# metronome_v1.net
KiCad netlist of a schematic drawn in EAGLE
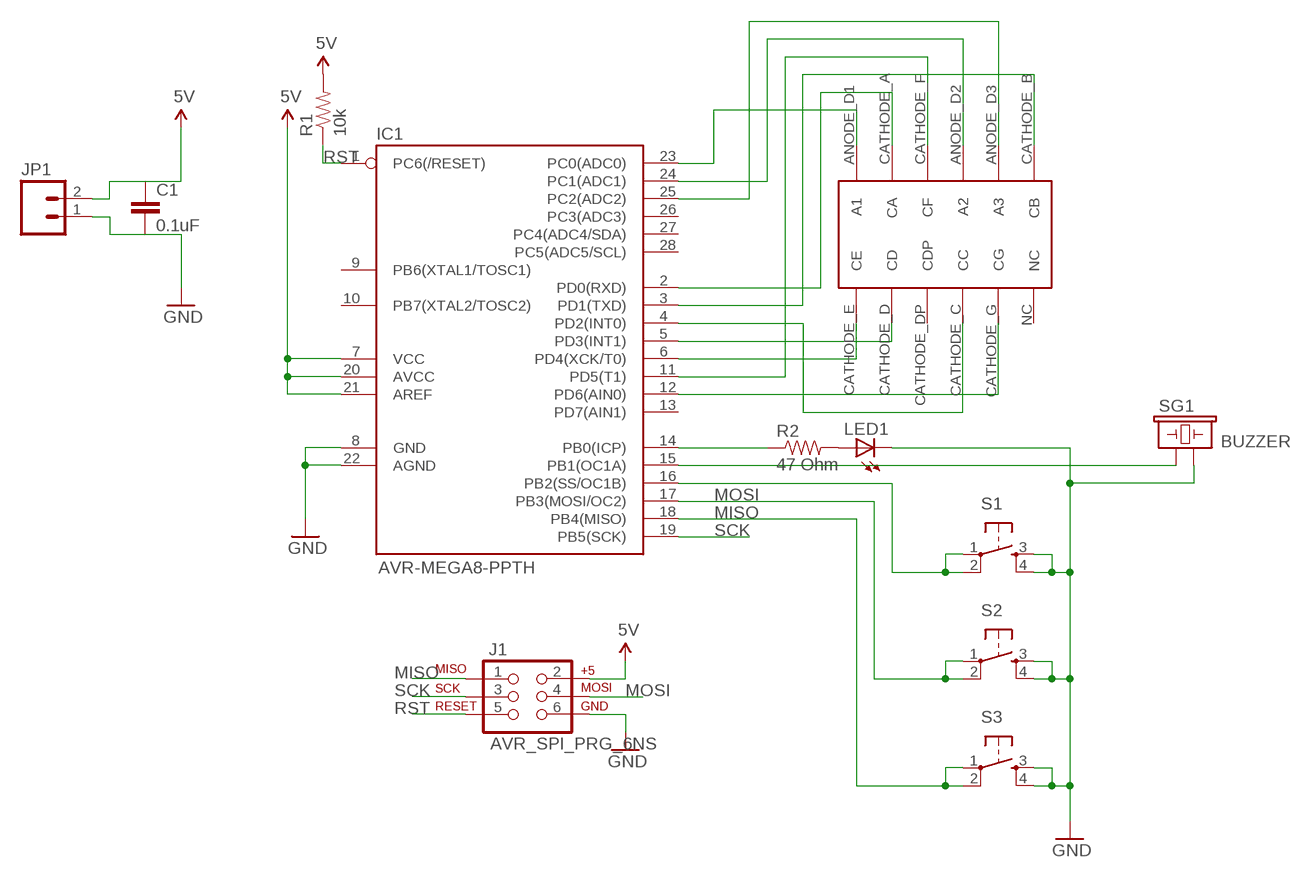
[diagram p0: schematic, sheet 1]

(export (version "E")
  (design (tool "Eeschema 10.0.6"))
  (components
    (comp (ref "C1")
      (value "0.1uF")
      (footprint "eagle-import:CAP-PTH-SMALL")
      (libsource (lib "eagle-import") (part "CAPPTH"))
    )
    (comp (ref "IC1")
      (value "AVR-MEGA8-PPTH")
      (footprint "eagle-import:DIL28-3")
      (libsource (lib "eagle-import") (part "AVR-MEGA8-PPTH"))
    )
    (comp (ref "J1")
      (value "AVR_SPI_PRG_6NS")
      (footprint "eagle-import:2X3-NS")
      (libsource (lib "eagle-import") (part "AVR_SPI_PRG_6NS"))
    )
    (comp (ref "JP1")
      (value "M02PTH3")
      (footprint "eagle-import:1X02_LONGPADS")
      (libsource (lib "eagle-import") (part "M02PTH3"))
    )
    (comp (ref "LED1")
      (value "LED5MM")
      (footprint "eagle-import:LED5MM")
      (libsource (lib "eagle-import") (part "LED5MM"))
    )
    (comp (ref "R1")
      (value "10k")
      (footprint "eagle-import:AXIAL-0.3")
      (libsource (lib "eagle-import") (part "RESISTORAXIAL-0.3"))
    )
    (comp (ref "R2")
      (value "47 Ohm")
      (footprint "eagle-import:AXIAL-0.3")
      (libsource (lib "eagle-import") (part "RESISTORAXIAL-0.3"))
    )
    (comp (ref "S1")
      (value "TAC_SWITCHPTH")
      (footprint "eagle-import:TACTILE-PTH")
      (libsource (lib "eagle-import") (part "TAC_SWITCHPTH"))
    )
    (comp (ref "S2")
      (value "TAC_SWITCHPTH")
      (footprint "eagle-import:TACTILE-PTH")
      (libsource (lib "eagle-import") (part "TAC_SWITCHPTH"))
    )
    (comp (ref "S3")
      (value "TAC_SWITCHPTH")
      (footprint "eagle-import:TACTILE-PTH")
      (libsource (lib "eagle-import") (part "TAC_SWITCHPTH"))
    )
    (comp (ref "SG1")
      (value "BUZZER")
      (footprint "eagle-import:BUZZER-762MM")
      (libsource (lib "eagle-import") (part "BUZZER"))
    )
    (comp (ref "U$1")
      (value "7-SEGMENT-3DIGIT-LTC516R")
      (footprint "eagle-import:7-SEGMENT-3DIGIT-LTC561R")
      (libsource (lib "eagle-import") (part "7-SEGMENT-3DIGIT-LTC516R"))
    )
  )
  (nets
    (net (code "1") (name "/MISO") (class "Default")
      (node (ref "IC1") (pin "18") (pinfunction "PB4(MISO)_18") (pintype "bidirectional"))
      (node (ref "J1") (pin "1") (pinfunction "1_1") (pintype "passive"))
      (node (ref "S3") (pin "1") (pinfunction "1_1") (pintype "passive"))
      (node (ref "S3") (pin "2") (pinfunction "2_2") (pintype "passive"))
    )
    (net (code "2") (name "/MOSI") (class "Default")
      (node (ref "IC1") (pin "17") (pinfunction "PB3(MOSI/OC2)_17") (pintype "bidirectional"))
      (node (ref "J1") (pin "4") (pinfunction "4_4") (pintype "passive"))
      (node (ref "S2") (pin "1") (pinfunction "1_1") (pintype "passive"))
      (node (ref "S2") (pin "2") (pinfunction "2_2") (pintype "passive"))
    )
    (net (code "3") (name "/RST") (class "Default")
      (node (ref "IC1") (pin "1") (pinfunction "PC6(/RESET)_1") (pintype "bidirectional"))
      (node (ref "J1") (pin "5") (pinfunction "5_5") (pintype "passive"))
      (node (ref "R1") (pin "P$1") (pinfunction "1_P$1") (pintype "passive"))
    )
    (net (code "4") (name "/SCK") (class "Default")
      (node (ref "IC1") (pin "19") (pinfunction "PB5(SCK)_19") (pintype "bidirectional"))
      (node (ref "J1") (pin "3") (pinfunction "3_3") (pintype "passive"))
    )
    (net (code "5") (name "5V") (class "Default")
      (node (ref "C1") (pin "1") (pinfunction "1_1") (pintype "passive"))
      (node (ref "IC1") (pin "20") (pinfunction "AVCC_20") (pintype "bidirectional"))
      (node (ref "IC1") (pin "21") (pinfunction "AREF_21") (pintype "bidirectional"))
      (node (ref "IC1") (pin "7") (pinfunction "VCC_7") (pintype "bidirectional"))
      (node (ref "J1") (pin "2") (pinfunction "2_2") (pintype "passive"))
      (node (ref "JP1") (pin "2") (pinfunction "2_2") (pintype "passive"))
      (node (ref "R1") (pin "P$2") (pinfunction "2_P$2") (pintype "passive"))
    )
    (net (code "6") (name "GND") (class "Default")
      (node (ref "C1") (pin "2") (pinfunction "2_2") (pintype "passive"))
      (node (ref "IC1") (pin "22") (pinfunction "AGND_22") (pintype "bidirectional"))
      (node (ref "IC1") (pin "8") (pinfunction "GND_8") (pintype "bidirectional"))
      (node (ref "J1") (pin "6") (pinfunction "6_6") (pintype "passive"))
      (node (ref "JP1") (pin "1") (pinfunction "1_1") (pintype "passive"))
      (node (ref "LED1") (pin "K") (pinfunction "C_K") (pintype "passive"))
      (node (ref "S1") (pin "3") (pinfunction "3_3") (pintype "passive"))
      (node (ref "S1") (pin "4") (pinfunction "4_4") (pintype "passive"))
      (node (ref "S2") (pin "3") (pinfunction "3_3") (pintype "passive"))
      (node (ref "S2") (pin "4") (pinfunction "4_4") (pintype "passive"))
      (node (ref "S3") (pin "3") (pinfunction "3_3") (pintype "passive"))
      (node (ref "S3") (pin "4") (pinfunction "4_4") (pintype "passive"))
      (node (ref "SG1") (pin "P$2") (pinfunction "2_P$2") (pintype "passive"))
    )
    (net (code "7") (name "Net-(IC1-PB0(ICP))") (class "Default")
      (node (ref "IC1") (pin "14") (pinfunction "PB0(ICP)_14") (pintype "bidirectional"))
      (node (ref "R2") (pin "P$1") (pinfunction "1_P$1") (pintype "passive"))
    )
    (net (code "8") (name "Net-(IC1-PB1(OC1A))") (class "Default")
      (node (ref "IC1") (pin "15") (pinfunction "PB1(OC1A)_15") (pintype "bidirectional"))
      (node (ref "SG1") (pin "P$1") (pinfunction "1_P$1") (pintype "passive"))
    )
    (net (code "9") (name "Net-(IC1-PB2(SS{slash}OC1B))") (class "Default")
      (node (ref "IC1") (pin "16") (pinfunction "PB2(SS/OC1B)_16") (pintype "bidirectional"))
      (node (ref "S1") (pin "1") (pinfunction "1_1") (pintype "passive"))
      (node (ref "S1") (pin "2") (pinfunction "2_2") (pintype "passive"))
    )
    (net (code "10") (name "Net-(IC1-PC0(ADC0))") (class "Default")
      (node (ref "IC1") (pin "23") (pinfunction "PC0(ADC0)_23") (pintype "bidirectional"))
      (node (ref "U$1") (pin "ANODE_D1") (pinfunction "A1_ANODE_D1") (pintype "bidirectional"))
    )
    (net (code "11") (name "Net-(IC1-PC1(ADC1))") (class "Default")
      (node (ref "IC1") (pin "24") (pinfunction "PC1(ADC1)_24") (pintype "bidirectional"))
      (node (ref "U$1") (pin "ANODE_D2") (pinfunction "A2_ANODE_D2") (pintype "bidirectional"))
    )
    (net (code "12") (name "Net-(IC1-PC2(ADC2))") (class "Default")
      (node (ref "IC1") (pin "25") (pinfunction "PC2(ADC2)_25") (pintype "bidirectional"))
      (node (ref "U$1") (pin "ANODE_D3") (pinfunction "A3_ANODE_D3") (pintype "bidirectional"))
    )
    (net (code "13") (name "Net-(IC1-PD0(RXD))") (class "Default")
      (node (ref "IC1") (pin "2") (pinfunction "PD0(RXD)_2") (pintype "bidirectional"))
      (node (ref "U$1") (pin "CATHODE_A") (pinfunction "CA_CATHODE_A") (pintype "bidirectional"))
    )
    (net (code "14") (name "Net-(IC1-PD1(TXD))") (class "Default")
      (node (ref "IC1") (pin "3") (pinfunction "PD1(TXD)_3") (pintype "bidirectional"))
      (node (ref "U$1") (pin "CATHODE_B") (pinfunction "CB_CATHODE_B") (pintype "bidirectional"))
    )
    (net (code "15") (name "Net-(IC1-PD2(INT0))") (class "Default")
      (node (ref "IC1") (pin "4") (pinfunction "PD2(INT0)_4") (pintype "bidirectional"))
      (node (ref "U$1") (pin "CATHODE_C") (pinfunction "CC_CATHODE_C") (pintype "bidirectional"))
    )
    (net (code "16") (name "Net-(IC1-PD3(INT1))") (class "Default")
      (node (ref "IC1") (pin "5") (pinfunction "PD3(INT1)_5") (pintype "bidirectional"))
      (node (ref "U$1") (pin "CATHODE_D") (pinfunction "CD_CATHODE_D") (pintype "bidirectional"))
    )
    (net (code "17") (name "Net-(IC1-PD4(XCK{slash}T0))") (class "Default")
      (node (ref "IC1") (pin "6") (pinfunction "PD4(XCK/T0)_6") (pintype "bidirectional"))
      (node (ref "U$1") (pin "CATHODE_E") (pinfunction "CE_CATHODE_E") (pintype "bidirectional"))
    )
    (net (code "18") (name "Net-(IC1-PD5(T1))") (class "Default")
      (node (ref "IC1") (pin "11") (pinfunction "PD5(T1)_11") (pintype "bidirectional"))
      (node (ref "U$1") (pin "CATHODE_F") (pinfunction "CF_CATHODE_F") (pintype "bidirectional"))
    )
    (net (code "19") (name "Net-(IC1-PD6(AIN0))") (class "Default")
      (node (ref "IC1") (pin "12") (pinfunction "PD6(AIN0)_12") (pintype "bidirectional"))
      (node (ref "U$1") (pin "CATHODE_G") (pinfunction "CG_CATHODE_G") (pintype "bidirectional"))
    )
    (net (code "20") (name "Net-(R2-2)") (class "Default")
      (node (ref "LED1") (pin "A") (pinfunction "A_A") (pintype "passive"))
      (node (ref "R2") (pin "P$2") (pinfunction "2_P$2") (pintype "passive"))
    )
    (net (code "21") (name "unconnected-(IC1-PB6(XTAL1{slash}TOSC1)-Pad9)") (class "Default")
      (node (ref "IC1") (pin "9") (pinfunction "PB6(XTAL1/TOSC1)_9") (pintype "bidirectional"))
    )
    (net (code "22") (name "unconnected-(IC1-PB7(XTAL2{slash}TOSC2)-Pad10)") (class "Default")
      (node (ref "IC1") (pin "10") (pinfunction "PB7(XTAL2/TOSC2)_10") (pintype "bidirectional"))
    )
    (net (code "23") (name "unconnected-(IC1-PC3(ADC3)-Pad26)") (class "Default")
      (node (ref "IC1") (pin "26") (pinfunction "PC3(ADC3)_26") (pintype "bidirectional"))
    )
    (net (code "24") (name "unconnected-(IC1-PC4(ADC4{slash}SDA)-Pad27)") (class "Default")
      (node (ref "IC1") (pin "27") (pinfunction "PC4(ADC4/SDA)_27") (pintype "bidirectional"))
    )
    (net (code "25") (name "unconnected-(IC1-PC5(ADC5{slash}SCL)-Pad28)") (class "Default")
      (node (ref "IC1") (pin "28") (pinfunction "PC5(ADC5/SCL)_28") (pintype "bidirectional"))
    )
    (net (code "26") (name "unconnected-(IC1-PD7(AIN1)-Pad13)") (class "Default")
      (node (ref "IC1") (pin "13") (pinfunction "PD7(AIN1)_13") (pintype "bidirectional"))
    )
    (net (code "27") (name "unconnected-(U$1-CDP-PadCATHODE_DP)") (class "Default")
      (node (ref "U$1") (pin "CATHODE_DP") (pinfunction "CDP_CATHODE_DP") (pintype "bidirectional"))
    )
    (net (code "28") (name "unconnected-(U$1-PadNC)") (class "Default")
      (node (ref "U$1") (pin "NC") (pinfunction "NC_NC") (pintype "bidirectional"))
    )
  )
)
